# BUS.net
KiCad netlist of a schematic drawn in Altium Designer
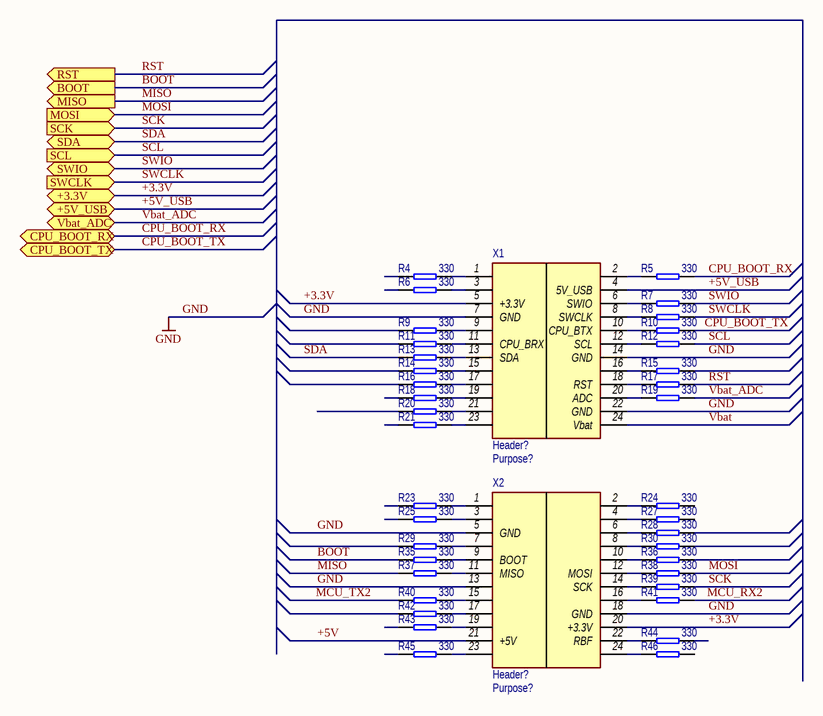
[diagram p0: BUS.SchDoc]

(export (version "E")
  (design (tool "Eeschema 10.0.6"))
  (components
    (comp (ref "R4")
      (value "330")
      (footprint "RES 0402")
      (description "Resistor")
      (fields (field (name "Comment") "RES 0402 330"))
      (libsource (lib "!main") (part "!Resistor"))
    )
    (comp (ref "R5")
      (value "330")
      (footprint "RES 0402")
      (description "Resistor")
      (fields (field (name "Comment") "RES 0402 330"))
      (libsource (lib "!main") (part "!Resistor"))
    )
    (comp (ref "R6")
      (value "330")
      (footprint "RES 0402")
      (description "Resistor")
      (fields (field (name "Comment") "RES 0402 330"))
      (libsource (lib "!main") (part "!Resistor"))
    )
    (comp (ref "R7")
      (value "330")
      (footprint "RES 0402")
      (description "Resistor")
      (fields (field (name "Comment") "RES 0402 330"))
      (libsource (lib "!main") (part "!Resistor"))
    )
    (comp (ref "R8")
      (value "330")
      (footprint "RES 0402")
      (description "Resistor")
      (fields (field (name "Comment") "RES 0402 330"))
      (libsource (lib "!main") (part "!Resistor"))
    )
    (comp (ref "R9")
      (value "330")
      (footprint "RES 0402")
      (description "Resistor")
      (fields (field (name "Comment") "RES 0402 330"))
      (libsource (lib "!main") (part "!Resistor"))
    )
    (comp (ref "R10")
      (value "330")
      (footprint "RES 0402")
      (description "Resistor")
      (fields (field (name "Comment") "RES 0402 330"))
      (libsource (lib "!main") (part "!Resistor"))
    )
    (comp (ref "R11")
      (value "330")
      (footprint "RES 0402")
      (description "Resistor")
      (fields (field (name "Comment") "RES 0402 330"))
      (libsource (lib "!main") (part "!Resistor"))
    )
    (comp (ref "R12")
      (value "330")
      (footprint "RES 0402")
      (description "Resistor")
      (fields (field (name "Comment") "RES 0402 330"))
      (libsource (lib "!main") (part "!Resistor"))
    )
    (comp (ref "R13")
      (value "330")
      (footprint "RES 0402")
      (description "Resistor")
      (fields (field (name "Comment") "RES 0402 330"))
      (libsource (lib "!main") (part "!Resistor"))
    )
    (comp (ref "R14")
      (value "330")
      (footprint "RES 0402")
      (description "Resistor")
      (fields (field (name "Comment") "RES 0402 330"))
      (libsource (lib "!main") (part "!Resistor"))
    )
    (comp (ref "R15")
      (value "330")
      (footprint "RES 0402")
      (description "Resistor")
      (fields (field (name "Comment") "RES 0402 330"))
      (libsource (lib "!main") (part "!Resistor"))
    )
    (comp (ref "R16")
      (value "330")
      (footprint "RES 0402")
      (description "Resistor")
      (fields (field (name "Comment") "RES 0402 330"))
      (libsource (lib "!main") (part "!Resistor"))
    )
    (comp (ref "R17")
      (value "330")
      (footprint "RES 0402")
      (description "Resistor")
      (fields (field (name "Comment") "RES 0402 330"))
      (libsource (lib "!main") (part "!Resistor"))
    )
    (comp (ref "R18")
      (value "330")
      (footprint "RES 0402")
      (description "Resistor")
      (fields (field (name "Comment") "RES 0402 330"))
      (libsource (lib "!main") (part "!Resistor"))
    )
    (comp (ref "R19")
      (value "330")
      (footprint "RES 0402")
      (description "Resistor")
      (fields (field (name "Comment") "RES 0402 330"))
      (libsource (lib "!main") (part "!Resistor"))
    )
    (comp (ref "R20")
      (value "330")
      (footprint "RES 0402")
      (description "Resistor")
      (fields (field (name "Comment") "RES 0402 330"))
      (libsource (lib "!main") (part "!Resistor"))
    )
    (comp (ref "R21")
      (value "330")
      (footprint "RES 0402")
      (description "Resistor")
      (fields (field (name "Comment") "RES 0402 330"))
      (libsource (lib "!main") (part "!Resistor"))
    )
    (comp (ref "R23")
      (value "330")
      (footprint "RES 0402")
      (description "Resistor")
      (fields (field (name "Comment") "RES 0402 330"))
      (libsource (lib "!main") (part "!Resistor"))
    )
    (comp (ref "R24")
      (value "330")
      (footprint "RES 0402")
      (description "Resistor")
      (fields (field (name "Comment") "RES 0402 330"))
      (libsource (lib "!main") (part "!Resistor"))
    )
    (comp (ref "R25")
      (value "330")
      (footprint "RES 0402")
      (description "Resistor")
      (fields (field (name "Comment") "RES 0402 330"))
      (libsource (lib "!main") (part "!Resistor"))
    )
    (comp (ref "R27")
      (value "330")
      (footprint "RES 0402")
      (description "Resistor")
      (fields (field (name "Comment") "RES 0402 330"))
      (libsource (lib "!main") (part "!Resistor"))
    )
    (comp (ref "R28")
      (value "330")
      (footprint "RES 0402")
      (description "Resistor")
      (fields (field (name "Comment") "RES 0402 330"))
      (libsource (lib "!main") (part "!Resistor"))
    )
    (comp (ref "R29")
      (value "330")
      (footprint "RES 0402")
      (description "Resistor")
      (fields (field (name "Comment") "RES 0402 330"))
      (libsource (lib "!main") (part "!Resistor"))
    )
    (comp (ref "R30")
      (value "330")
      (footprint "RES 0402")
      (description "Resistor")
      (fields (field (name "Comment") "RES 0402 330"))
      (libsource (lib "!main") (part "!Resistor"))
    )
    (comp (ref "R35")
      (value "330")
      (footprint "RES 0402")
      (description "Resistor")
      (fields (field (name "Comment") "RES 0402 330"))
      (libsource (lib "!main") (part "!Resistor"))
    )
    (comp (ref "R36")
      (value "330")
      (footprint "RES 0402")
      (description "Resistor")
      (fields (field (name "Comment") "RES 0402 330"))
      (libsource (lib "!main") (part "!Resistor"))
    )
    (comp (ref "R37")
      (value "330")
      (footprint "RES 0402")
      (description "Resistor")
      (fields (field (name "Comment") "RES 0402 330"))
      (libsource (lib "!main") (part "!Resistor"))
    )
    (comp (ref "R38")
      (value "330")
      (footprint "RES 0402")
      (description "Resistor")
      (fields (field (name "Comment") "RES 0402 330"))
      (libsource (lib "!main") (part "!Resistor"))
    )
    (comp (ref "R39")
      (value "330")
      (footprint "RES 0402")
      (description "Resistor")
      (fields (field (name "Comment") "RES 0402 330"))
      (libsource (lib "!main") (part "!Resistor"))
    )
    (comp (ref "R40")
      (value "330")
      (footprint "RES 0402")
      (description "Resistor")
      (fields (field (name "Comment") "RES 0402 330"))
      (libsource (lib "!main") (part "!Resistor"))
    )
    (comp (ref "R41")
      (value "330")
      (footprint "RES 0402")
      (description "Resistor")
      (fields (field (name "Comment") "RES 0402 330"))
      (libsource (lib "!main") (part "!Resistor"))
    )
    (comp (ref "R42")
      (value "330")
      (footprint "RES 0402")
      (description "Resistor")
      (fields (field (name "Comment") "RES 0402 330"))
      (libsource (lib "!main") (part "!Resistor"))
    )
    (comp (ref "R43")
      (value "330")
      (footprint "RES 0402")
      (description "Resistor")
      (fields (field (name "Comment") "RES 0402 330"))
      (libsource (lib "!main") (part "!Resistor"))
    )
    (comp (ref "R44")
      (value "330")
      (footprint "RES 0402")
      (description "Resistor")
      (fields (field (name "Comment") "RES 0402 330"))
      (libsource (lib "!main") (part "!Resistor"))
    )
    (comp (ref "R45")
      (value "330")
      (footprint "RES 0402")
      (description "Resistor")
      (fields (field (name "Comment") "RES 0402 330"))
      (libsource (lib "!main") (part "!Resistor"))
    )
    (comp (ref "R46")
      (value "330")
      (footprint "RES 0402")
      (description "Resistor")
      (fields (field (name "Comment") "RES 0402 330"))
      (libsource (lib "!main") (part "!Resistor"))
    )
    (comp (ref "X1")
      (value "Header?")
      (footprint "PICOSAT_CNN")
      (description "10x2 header")
      (fields (field (name "PURPOSE") "Purpose?"))
      (libsource (lib "connectors") (part "Header 2x12"))
    )
    (comp (ref "X2")
      (value "Header?")
      (footprint "PICOSAT_CNN")
      (description "10x2 header")
      (fields (field (name "PURPOSE") "Purpose?"))
      (libsource (lib "connectors") (part "Header 2x12"))
    )
  )
  (nets
    (net (code "1") (name "/+3.3V") (class "Default")
      (node (ref "X1") (pin "5") (pinfunction "+3.3V_5") (pintype "passive"))
      (node (ref "X2") (pin "20") (pinfunction "ADC_20") (pintype "passive"))
    )
    (net (code "2") (name "/+5V") (class "Default") (node (ref "X2") (pin "21") (pintype "passive")))
    (net (code "3") (name "/+5V_USB") (class "Default")
      (node (ref "X1") (pin "4") (pinfunction "5V_USB_4") (pintype "passive"))
    )
    (net (code "4") (name "/BOOT") (class "Default")
      (node (ref "R35") (pin "1") (pinfunction "11_1") (pintype "passive"))
    )
    (net (code "5") (name "/CPU_BOOT_RX") (class "Default")
      (node (ref "R5") (pin "2") (pinfunction "12_2") (pintype "passive"))
    )
    (net (code "6") (name "/CPU_BOOT_TX") (class "Default")
      (node (ref "R10") (pin "2") (pinfunction "12_2") (pintype "passive"))
    )
    (net (code "8") (name "/MCU_RX2") (class "Default")
      (node (ref "R41") (pin "2") (pinfunction "12_2") (pintype "passive"))
    )
    (net (code "9") (name "/MCU_TX2") (class "Default")
      (node (ref "R40") (pin "1") (pinfunction "11_1") (pintype "passive"))
    )
    (net (code "10") (name "/MISO") (class "Default")
      (node (ref "R37") (pin "1") (pinfunction "11_1") (pintype "passive"))
    )
    (net (code "11") (name "/MOSI") (class "Default")
      (node (ref "R38") (pin "2") (pinfunction "12_2") (pintype "passive"))
    )
    (net (code "13") (name "/RST") (class "Default")
      (node (ref "R17") (pin "2") (pinfunction "12_2") (pintype "passive"))
    )
    (net (code "14") (name "/SCK") (class "Default")
      (node (ref "R39") (pin "2") (pinfunction "12_2") (pintype "passive"))
    )
    (net (code "15") (name "/SCL") (class "Default")
      (node (ref "R12") (pin "2") (pinfunction "12_2") (pintype "passive"))
    )
    (net (code "16") (name "/SDA") (class "Default")
      (node (ref "R13") (pin "1") (pinfunction "11_1") (pintype "passive"))
    )
    (net (code "17") (name "/SWCLK") (class "Default")
      (node (ref "R8") (pin "2") (pinfunction "12_2") (pintype "passive"))
    )
    (net (code "19") (name "/SWIO") (class "Default")
      (node (ref "R7") (pin "2") (pinfunction "12_2") (pintype "passive"))
    )
    (net (code "20") (name "/Vbat") (class "Default")
      (node (ref "X1") (pin "24") (pinfunction "Vbat_24") (pintype "passive"))
    )
    (net (code "21") (name "/Vbat_ADC") (class "Default")
      (node (ref "R19") (pin "2") (pinfunction "12_2") (pintype "passive"))
    )
    (net (code "22") (name "GND") (class "Default")
      (node (ref "X1") (pin "14") (pinfunction "GND_14") (pintype "passive"))
      (node (ref "X1") (pin "22") (pinfunction "GND_22") (pintype "passive"))
      (node (ref "X1") (pin "7") (pinfunction "GND_7") (pintype "passive"))
      (node (ref "X2") (pin "13") (pinfunction "SDA_13") (pintype "passive"))
      (node (ref "X2") (pin "18") (pinfunction "RST_18") (pintype "passive"))
      (node (ref "X2") (pin "5") (pinfunction "+3.3V_5") (pintype "passive"))
    )
    (net (code "23") (name "Net-(R4-12)") (class "Default")
      (node (ref "R4") (pin "2") (pinfunction "12_2") (pintype "passive"))
      (node (ref "X1") (pin "1") (pintype "passive"))
    )
    (net (code "24") (name "Net-(R5-11)") (class "Default")
      (node (ref "R5") (pin "1") (pinfunction "11_1") (pintype "passive"))
      (node (ref "X1") (pin "2") (pintype "passive"))
    )
    (net (code "25") (name "Net-(R6-12)") (class "Default")
      (node (ref "R6") (pin "2") (pinfunction "12_2") (pintype "passive"))
      (node (ref "X1") (pin "3") (pintype "passive"))
    )
    (net (code "26") (name "Net-(R7-11)") (class "Default")
      (node (ref "R7") (pin "1") (pinfunction "11_1") (pintype "passive"))
      (node (ref "X1") (pin "6") (pinfunction "SWIO_6") (pintype "passive"))
    )
    (net (code "27") (name "Net-(R8-11)") (class "Default")
      (node (ref "R8") (pin "1") (pinfunction "11_1") (pintype "passive"))
      (node (ref "X1") (pin "8") (pinfunction "SWCLK_8") (pintype "passive"))
    )
    (net (code "28") (name "Net-(R9-12)") (class "Default")
      (node (ref "R9") (pin "2") (pinfunction "12_2") (pintype "passive"))
      (node (ref "X1") (pin "9") (pintype "passive"))
    )
    (net (code "29") (name "Net-(R10-11)") (class "Default")
      (node (ref "R10") (pin "1") (pinfunction "11_1") (pintype "passive"))
      (node (ref "X1") (pin "10") (pinfunction "CPU_BTX_10") (pintype "passive"))
    )
    (net (code "30") (name "Net-(R11-12)") (class "Default")
      (node (ref "R11") (pin "2") (pinfunction "12_2") (pintype "passive"))
      (node (ref "X1") (pin "11") (pinfunction "CPU_BRX_11") (pintype "passive"))
    )
    (net (code "31") (name "Net-(R12-11)") (class "Default")
      (node (ref "R12") (pin "1") (pinfunction "11_1") (pintype "passive"))
      (node (ref "X1") (pin "12") (pinfunction "SCL_12") (pintype "passive"))
    )
    (net (code "32") (name "Net-(R13-12)") (class "Default")
      (node (ref "R13") (pin "2") (pinfunction "12_2") (pintype "passive"))
      (node (ref "X1") (pin "13") (pinfunction "SDA_13") (pintype "passive"))
    )
    (net (code "33") (name "Net-(R14-12)") (class "Default")
      (node (ref "R14") (pin "2") (pinfunction "12_2") (pintype "passive"))
      (node (ref "X1") (pin "15") (pintype "passive"))
    )
    (net (code "34") (name "Net-(R15-11)") (class "Default")
      (node (ref "R15") (pin "1") (pinfunction "11_1") (pintype "passive"))
      (node (ref "X1") (pin "16") (pintype "passive"))
    )
    (net (code "35") (name "Net-(R16-12)") (class "Default")
      (node (ref "R16") (pin "2") (pinfunction "12_2") (pintype "passive"))
      (node (ref "X1") (pin "17") (pintype "passive"))
    )
    (net (code "36") (name "Net-(R17-11)") (class "Default")
      (node (ref "R17") (pin "1") (pinfunction "11_1") (pintype "passive"))
      (node (ref "X1") (pin "18") (pinfunction "RST_18") (pintype "passive"))
    )
    (net (code "37") (name "Net-(R18-12)") (class "Default")
      (node (ref "R18") (pin "2") (pinfunction "12_2") (pintype "passive"))
      (node (ref "X1") (pin "19") (pintype "passive"))
    )
    (net (code "38") (name "Net-(R19-11)") (class "Default")
      (node (ref "R19") (pin "1") (pinfunction "11_1") (pintype "passive"))
      (node (ref "X1") (pin "20") (pinfunction "ADC_20") (pintype "passive"))
    )
    (net (code "39") (name "Net-(R20-12)") (class "Default")
      (node (ref "R20") (pin "2") (pinfunction "12_2") (pintype "passive"))
      (node (ref "X1") (pin "21") (pintype "passive"))
    )
    (net (code "40") (name "Net-(R21-12)") (class "Default")
      (node (ref "R21") (pin "2") (pinfunction "12_2") (pintype "passive"))
      (node (ref "X1") (pin "23") (pintype "passive"))
    )
    (net (code "41") (name "Net-(R23-12)") (class "Default")
      (node (ref "R23") (pin "2") (pinfunction "12_2") (pintype "passive"))
      (node (ref "X2") (pin "1") (pintype "passive"))
    )
    (net (code "42") (name "Net-(R24-11)") (class "Default")
      (node (ref "R24") (pin "1") (pinfunction "11_1") (pintype "passive"))
      (node (ref "X2") (pin "2") (pintype "passive"))
    )
    (net (code "43") (name "Net-(R25-12)") (class "Default")
      (node (ref "R25") (pin "2") (pinfunction "12_2") (pintype "passive"))
      (node (ref "X2") (pin "3") (pintype "passive"))
    )
    (net (code "44") (name "Net-(R27-11)") (class "Default")
      (node (ref "R27") (pin "1") (pinfunction "11_1") (pintype "passive"))
      (node (ref "X2") (pin "4") (pinfunction "5V_USB_4") (pintype "passive"))
    )
    (net (code "45") (name "Net-(R28-11)") (class "Default")
      (node (ref "R28") (pin "1") (pinfunction "11_1") (pintype "passive"))
      (node (ref "X2") (pin "6") (pinfunction "SWIO_6") (pintype "passive"))
    )
    (net (code "46") (name "Net-(R29-12)") (class "Default")
      (node (ref "R29") (pin "2") (pinfunction "12_2") (pintype "passive"))
      (node (ref "X2") (pin "7") (pinfunction "GND_7") (pintype "passive"))
    )
    (net (code "47") (name "Net-(R30-11)") (class "Default")
      (node (ref "R30") (pin "1") (pinfunction "11_1") (pintype "passive"))
      (node (ref "X2") (pin "8") (pinfunction "SWCLK_8") (pintype "passive"))
    )
    (net (code "48") (name "Net-(R35-12)") (class "Default")
      (node (ref "R35") (pin "2") (pinfunction "12_2") (pintype "passive"))
      (node (ref "X2") (pin "9") (pintype "passive"))
    )
    (net (code "49") (name "Net-(R36-11)") (class "Default")
      (node (ref "R36") (pin "1") (pinfunction "11_1") (pintype "passive"))
      (node (ref "X2") (pin "10") (pinfunction "CPU_BTX_10") (pintype "passive"))
    )
    (net (code "50") (name "Net-(R37-12)") (class "Default")
      (node (ref "R37") (pin "2") (pinfunction "12_2") (pintype "passive"))
      (node (ref "X2") (pin "11") (pinfunction "CPU_BRX_11") (pintype "passive"))
    )
    (net (code "51") (name "Net-(R38-11)") (class "Default")
      (node (ref "R38") (pin "1") (pinfunction "11_1") (pintype "passive"))
      (node (ref "X2") (pin "12") (pinfunction "SCL_12") (pintype "passive"))
    )
    (net (code "52") (name "Net-(R39-11)") (class "Default")
      (node (ref "R39") (pin "1") (pinfunction "11_1") (pintype "passive"))
      (node (ref "X2") (pin "14") (pinfunction "GND_14") (pintype "passive"))
    )
    (net (code "53") (name "Net-(R40-12)") (class "Default")
      (node (ref "R40") (pin "2") (pinfunction "12_2") (pintype "passive"))
      (node (ref "X2") (pin "15") (pintype "passive"))
    )
    (net (code "54") (name "Net-(R41-11)") (class "Default")
      (node (ref "R41") (pin "1") (pinfunction "11_1") (pintype "passive"))
      (node (ref "X2") (pin "16") (pintype "passive"))
    )
    (net (code "55") (name "Net-(R42-12)") (class "Default")
      (node (ref "R42") (pin "2") (pinfunction "12_2") (pintype "passive"))
      (node (ref "X2") (pin "17") (pintype "passive"))
    )
    (net (code "56") (name "Net-(R43-12)") (class "Default")
      (node (ref "R43") (pin "2") (pinfunction "12_2") (pintype "passive"))
      (node (ref "X2") (pin "19") (pintype "passive"))
    )
    (net (code "57") (name "Net-(R44-11)") (class "Default")
      (node (ref "R44") (pin "1") (pinfunction "11_1") (pintype "passive"))
      (node (ref "X2") (pin "22") (pinfunction "GND_22") (pintype "passive"))
    )
    (net (code "58") (name "Net-(R45-12)") (class "Default")
      (node (ref "R45") (pin "2") (pinfunction "12_2") (pintype "passive"))
      (node (ref "X2") (pin "23") (pintype "passive"))
    )
    (net (code "59") (name "Net-(R46-11)") (class "Default")
      (node (ref "R46") (pin "1") (pinfunction "11_1") (pintype "passive"))
      (node (ref "X2") (pin "24") (pinfunction "Vbat_24") (pintype "passive"))
    )
    (net (code "60") (name "unconnected-(R4-11-Pad1)") (class "Default")
      (node (ref "R4") (pin "1") (pinfunction "11_1") (pintype "passive"))
    )
    (net (code "61") (name "unconnected-(R6-11-Pad1)") (class "Default")
      (node (ref "R6") (pin "1") (pinfunction "11_1") (pintype "passive"))
    )
    (net (code "62") (name "unconnected-(R9-11-Pad1)") (class "Default")
      (node (ref "R9") (pin "1") (pinfunction "11_1") (pintype "passive"))
    )
    (net (code "63") (name "unconnected-(R11-11-Pad1)") (class "Default")
      (node (ref "R11") (pin "1") (pinfunction "11_1") (pintype "passive"))
    )
    (net (code "64") (name "unconnected-(R14-11-Pad1)") (class "Default")
      (node (ref "R14") (pin "1") (pinfunction "11_1") (pintype "passive"))
    )
    (net (code "65") (name "unconnected-(R15-12-Pad2)") (class "Default")
      (node (ref "R15") (pin "2") (pinfunction "12_2") (pintype "passive"))
    )
    (net (code "66") (name "unconnected-(R16-11-Pad1)") (class "Default")
      (node (ref "R16") (pin "1") (pinfunction "11_1") (pintype "passive"))
    )
    (net (code "67") (name "unconnected-(R18-11-Pad1)") (class "Default")
      (node (ref "R18") (pin "1") (pinfunction "11_1") (pintype "passive"))
    )
    (net (code "68") (name "unconnected-(R20-11-Pad1)") (class "Default")
      (node (ref "R20") (pin "1") (pinfunction "11_1") (pintype "passive"))
    )
    (net (code "69") (name "unconnected-(R21-11-Pad1)") (class "Default")
      (node (ref "R21") (pin "1") (pinfunction "11_1") (pintype "passive"))
    )
    (net (code "70") (name "unconnected-(R23-11-Pad1)") (class "Default")
      (node (ref "R23") (pin "1") (pinfunction "11_1") (pintype "passive"))
    )
    (net (code "71") (name "unconnected-(R24-12-Pad2)") (class "Default")
      (node (ref "R24") (pin "2") (pinfunction "12_2") (pintype "passive"))
    )
    (net (code "72") (name "unconnected-(R25-11-Pad1)") (class "Default")
      (node (ref "R25") (pin "1") (pinfunction "11_1") (pintype "passive"))
    )
    (net (code "73") (name "unconnected-(R27-12-Pad2)") (class "Default")
      (node (ref "R27") (pin "2") (pinfunction "12_2") (pintype "passive"))
    )
    (net (code "74") (name "unconnected-(R28-12-Pad2)") (class "Default")
      (node (ref "R28") (pin "2") (pinfunction "12_2") (pintype "passive"))
    )
    (net (code "75") (name "unconnected-(R29-11-Pad1)") (class "Default")
      (node (ref "R29") (pin "1") (pinfunction "11_1") (pintype "passive"))
    )
    (net (code "76") (name "unconnected-(R30-12-Pad2)") (class "Default")
      (node (ref "R30") (pin "2") (pinfunction "12_2") (pintype "passive"))
    )
    (net (code "77") (name "unconnected-(R36-12-Pad2)") (class "Default")
      (node (ref "R36") (pin "2") (pinfunction "12_2") (pintype "passive"))
    )
    (net (code "78") (name "unconnected-(R42-11-Pad1)") (class "Default")
      (node (ref "R42") (pin "1") (pinfunction "11_1") (pintype "passive"))
    )
    (net (code "79") (name "unconnected-(R43-11-Pad1)") (class "Default")
      (node (ref "R43") (pin "1") (pinfunction "11_1") (pintype "passive"))
    )
    (net (code "80") (name "unconnected-(R44-12-Pad2)") (class "Default")
      (node (ref "R44") (pin "2") (pinfunction "12_2") (pintype "passive"))
    )
    (net (code "81") (name "unconnected-(R45-11-Pad1)") (class "Default")
      (node (ref "R45") (pin "1") (pinfunction "11_1") (pintype "passive"))
    )
    (net (code "82") (name "unconnected-(R46-12-Pad2)") (class "Default")
      (node (ref "R46") (pin "2") (pinfunction "12_2") (pintype "passive"))
    )
  )
)
